# RS_485_MAX3352_TXLED.net
KiCad netlist of a schematic drawn in Altium Designer
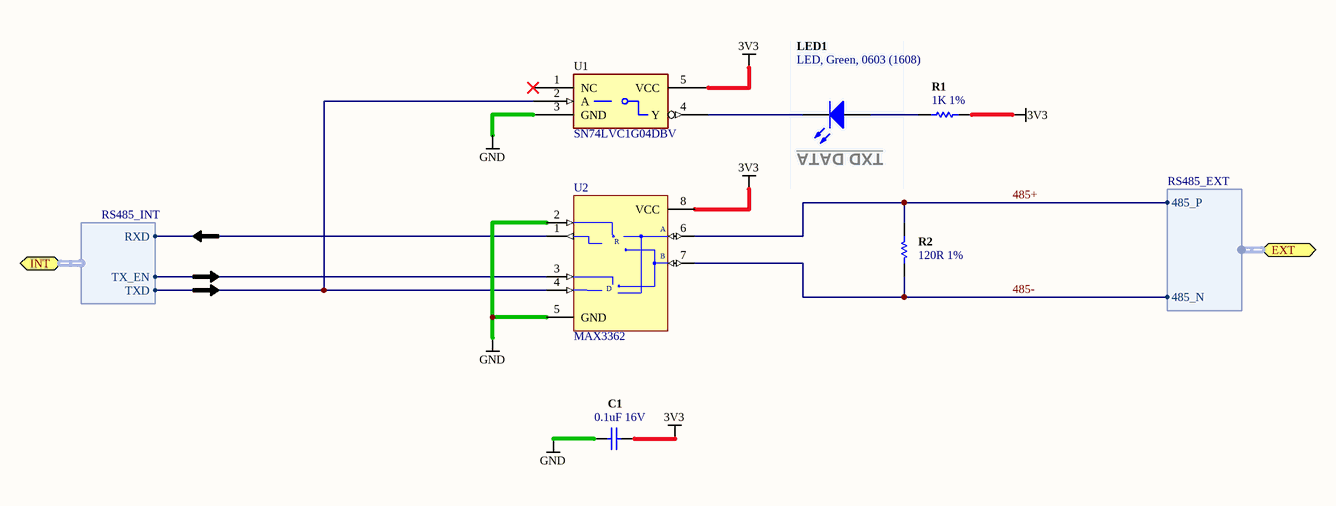
[diagram p0: RS_485_MAX3352_TXLED.SchDoc]

(export (version "E")
  (design (tool "Eeschema 10.0.6"))
  (components
    (comp (ref "C1")
      (value "0.1uF 16V")
      (footprint "CAPC1005-STAR")
      (description "Capacitor, Ceramic, 0.1uF 10% 16V 0402 (1005) X7R")
      (fields (field (name "TOLERANCE") "10 %"))
      (libsource (lib "altium-import") (part "root_3_CAP-NP_"))
    )
    (comp (ref "LED1")
      (value "LED, Green, 0603 (1608)")
      (footprint "0603LED")
      (libsource (lib "AltiumDesignLibrary") (part "DIO-LED-1S"))
    )
    (comp (ref "R1")
      (value "1K 1%")
      (footprint "RESC1005-STAR")
      (description "Resistor, 1K 1% 0402 (1005)")
      (fields (field (name "TOLERANCE") "1 %"))
      (libsource (lib "AltiumDesignLibrary") (part "RES"))
    )
    (comp (ref "R2")
      (value "120R 1%")
      (footprint "RESC1005-STAR")
      (description "Resistor, 120R 1% 0402 (1005)")
      (fields (field (name "TOLERANCE") "1 %"))
      (libsource (lib "AltiumDesignLibrary") (part "RES"))
    )
    (comp (ref "U1")
      (value "SN74LVC1G04DBV")
      (footprint "SOT95P280-5")
      (description "SN74LVC1G04DBV, Single Inverter Gate, 1.65-V to 5.5-V")
      (libsource (lib "AltiumDesignLibrary") (part "SN74LVC1G04DBV"))
    )
    (comp (ref "U2")
      (value "MAX3362")
      (footprint "SOT23-8")
      (description "MAX3362 3.3V, High-Speed, RS-485/RS-422 Transceiver in  SOT Package")
      (libsource (lib "AltiumDesignLibrary") (part "MAX3362"))
    )
  )
  (nets
    (net (code "3") (name "/485+") (class "Default")
      (node (ref "R2") (pin "2") (pinfunction "2_2") (pintype "passive"))
      (node (ref "U2") (pin "6") (pinfunction "A_6") (pintype "bidirectional"))
    )
    (net (code "4") (name "/485-") (class "Default")
      (node (ref "R2") (pin "1") (pinfunction "1_1") (pintype "passive"))
      (node (ref "U2") (pin "7") (pinfunction "B_7") (pintype "bidirectional"))
    )
    (net (code "5") (name "/RXD") (class "Default")
      (node (ref "U2") (pin "1") (pinfunction "RO_1") (pintype "output"))
    )
    (net (code "6") (name "/TXD") (class "Default")
      (node (ref "U1") (pin "2") (pinfunction "A_2") (pintype "input"))
      (node (ref "U2") (pin "4") (pinfunction "DI_4") (pintype "input"))
    )
    (net (code "7") (name "/TX_EN") (class "Default")
      (node (ref "U2") (pin "3") (pinfunction "DE_3") (pintype "input"))
    )
    (net (code "10") (name "3V3") (class "Default")
      (node (ref "C1") (pin "1") (pinfunction "1_1") (pintype "passive"))
      (node (ref "R1") (pin "1") (pinfunction "1_1") (pintype "passive"))
      (node (ref "U1") (pin "5") (pinfunction "VCC_5") (pintype "power_in"))
      (node (ref "U2") (pin "8") (pinfunction "VCC_8") (pintype "power_in"))
    )
    (net (code "11") (name "GND") (class "Default")
      (node (ref "C1") (pin "2") (pinfunction "2_2") (pintype "passive"))
      (node (ref "U1") (pin "3") (pinfunction "GND_3") (pintype "power_in"))
      (node (ref "U2") (pin "2") (pinfunction "~{RE}_2") (pintype "input"))
      (node (ref "U2") (pin "5") (pinfunction "GND_5") (pintype "power_in"))
    )
    (net (code "12") (name "Net-(LED1-A)") (class "Default")
      (node (ref "LED1") (pin "1") (pinfunction "A_1") (pintype "passive"))
      (node (ref "R1") (pin "2") (pinfunction "2_2") (pintype "passive"))
    )
    (net (code "13") (name "Net-(LED1-K)") (class "Default")
      (node (ref "LED1") (pin "2") (pinfunction "K_2") (pintype "passive"))
      (node (ref "U1") (pin "4") (pinfunction "Y_4") (pintype "output"))
    )
    (net (code "14") (name "unconnected-(U1-NC-Pad1)") (class "Default")
      (node (ref "U1") (pin "1") (pinfunction "NC_1") (pintype "passive+no_connect"))
    )
  )
)
